# Signal_isolator.net
KiCad netlist of a schematic drawn in Altium Designer
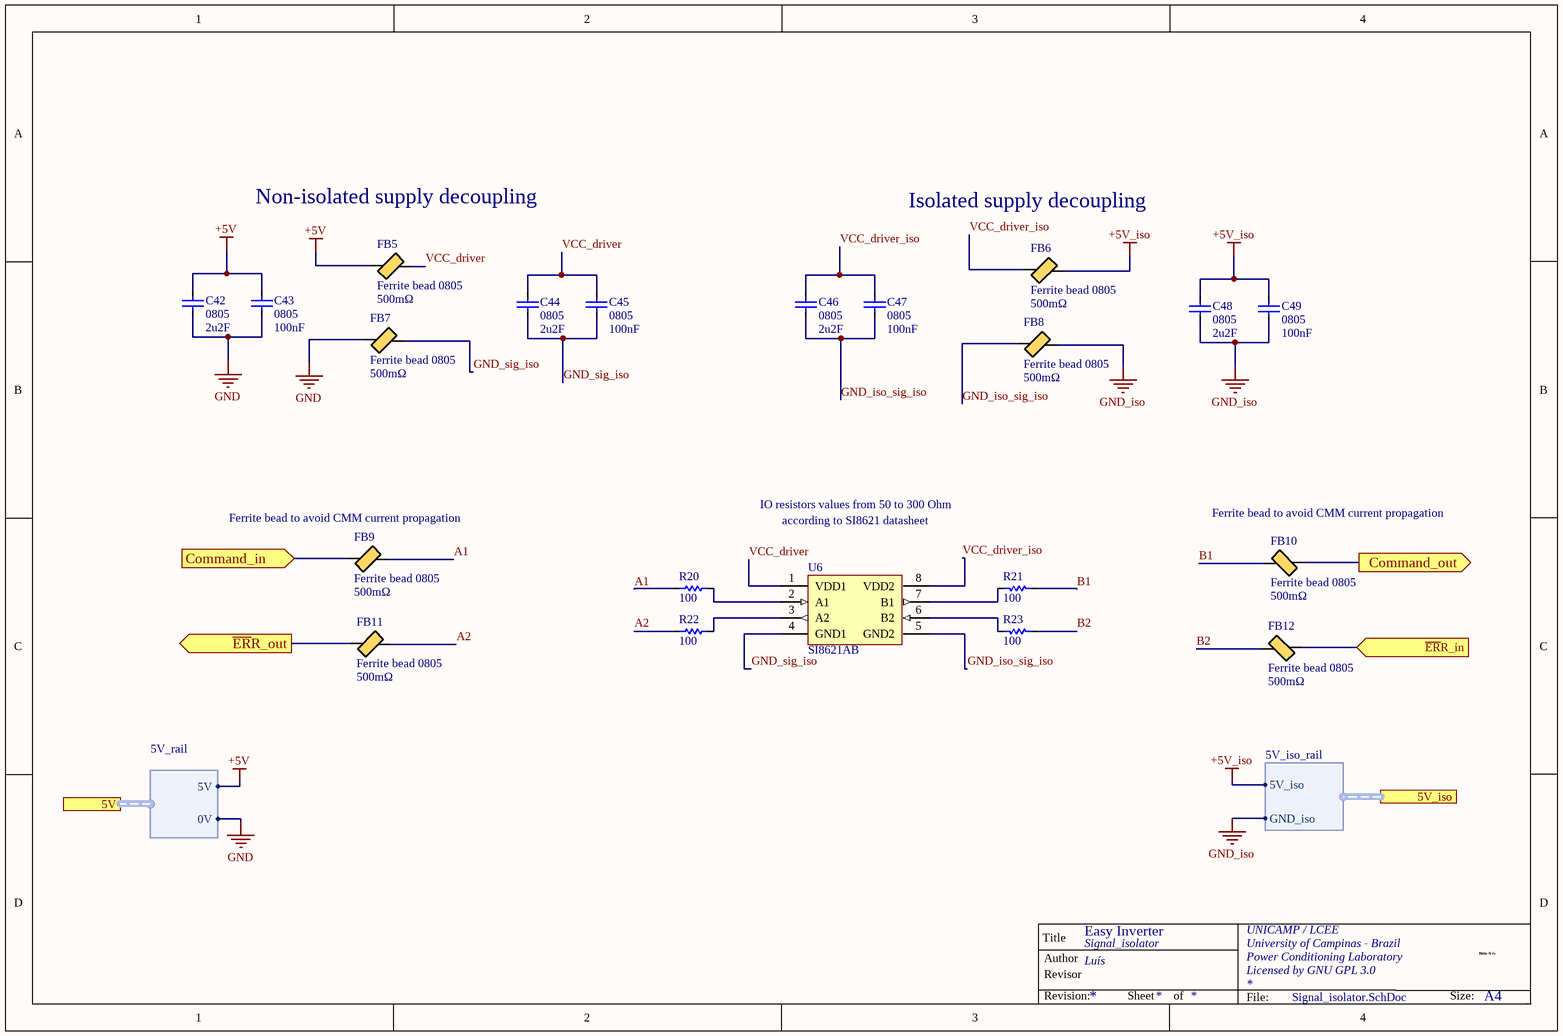
[diagram p0: Signal_isolator.SchDoc]

(export (version "E")
  (design (tool "Eeschema 10.0.6"))
  (components
    (comp (ref "C42")
      (value "0805")
      (footprint "Capacitor 0805")
      (description "SMD ceramic capacitor 0805")
      (fields (field (name "ALTIUM_VALUE") "2u2F"))
      (libsource (lib "EdgeInverter_library") (part "Capacitor 0805"))
    )
    (comp (ref "C43")
      (value "0805")
      (footprint "Capacitor 0805")
      (description "SMD ceramic capacitor 0805")
      (fields (field (name "ALTIUM_VALUE") "100nF"))
      (libsource (lib "EdgeInverter_library") (part "Capacitor 0805"))
    )
    (comp (ref "C44")
      (value "0805")
      (footprint "Capacitor 0805")
      (description "SMD ceramic capacitor 0805")
      (fields (field (name "ALTIUM_VALUE") "2u2F"))
      (libsource (lib "EdgeInverter_library") (part "Capacitor 0805"))
    )
    (comp (ref "C45")
      (value "0805")
      (footprint "Capacitor 0805")
      (description "SMD ceramic capacitor 0805")
      (fields (field (name "ALTIUM_VALUE") "100nF"))
      (libsource (lib "EdgeInverter_library") (part "Capacitor 0805"))
    )
    (comp (ref "C46")
      (value "0805")
      (footprint "Capacitor 0805")
      (description "SMD ceramic capacitor 0805")
      (fields (field (name "ALTIUM_VALUE") "2u2F"))
      (libsource (lib "EdgeInverter_library") (part "Capacitor 0805"))
    )
    (comp (ref "C47")
      (value "0805")
      (footprint "Capacitor 0805")
      (description "SMD ceramic capacitor 0805")
      (fields (field (name "ALTIUM_VALUE") "100nF"))
      (libsource (lib "EdgeInverter_library") (part "Capacitor 0805"))
    )
    (comp (ref "C48")
      (value "0805")
      (footprint "Capacitor 0805")
      (description "SMD ceramic capacitor 0805")
      (fields (field (name "ALTIUM_VALUE") "2u2F"))
      (libsource (lib "EdgeInverter_library") (part "Capacitor 0805"))
    )
    (comp (ref "C49")
      (value "0805")
      (footprint "Capacitor 0805")
      (description "SMD ceramic capacitor 0805")
      (fields (field (name "ALTIUM_VALUE") "100nF"))
      (libsource (lib "EdgeInverter_library") (part "Capacitor 0805"))
    )
    (comp (ref "FB5")
      (value "Ferrite bead 0805")
      (footprint "Bead 0805")
      (description "Ferrite bead chip 0805")
      (fields (field (name "DC RESISTANCE") "500mΩ"))
      (libsource (lib "EdgeInverter_library") (part "Ferrite_bead"))
    )
    (comp (ref "FB6")
      (value "Ferrite bead 0805")
      (footprint "Bead 0805")
      (description "Ferrite bead chip 0805")
      (fields (field (name "DC RESISTANCE") "500mΩ"))
      (libsource (lib "EdgeInverter_library") (part "Ferrite_bead"))
    )
    (comp (ref "FB7")
      (value "Ferrite bead 0805")
      (footprint "Bead 0805")
      (description "Ferrite bead chip 0805")
      (fields (field (name "DC RESISTANCE") "500mΩ"))
      (libsource (lib "EdgeInverter_library") (part "Ferrite_bead"))
    )
    (comp (ref "FB8")
      (value "Ferrite bead 0805")
      (footprint "Bead 0805")
      (description "Ferrite bead chip 0805")
      (fields (field (name "DC RESISTANCE") "500mΩ"))
      (libsource (lib "EdgeInverter_library") (part "Ferrite_bead"))
    )
    (comp (ref "FB9")
      (value "Ferrite bead 0805")
      (footprint "Bead 0805")
      (description "Ferrite bead chip 0805")
      (fields (field (name "DC RESISTANCE") "500mΩ"))
      (libsource (lib "EdgeInverter_library") (part "Ferrite_bead"))
    )
    (comp (ref "FB10")
      (value "Ferrite bead 0805")
      (footprint "Bead 0805")
      (description "Ferrite bead chip 0805")
      (fields (field (name "DC RESISTANCE") "500mΩ"))
      (libsource (lib "EdgeInverter_library") (part "Ferrite_bead"))
    )
    (comp (ref "FB11")
      (value "Ferrite bead 0805")
      (footprint "Bead 0805")
      (description "Ferrite bead chip 0805")
      (fields (field (name "DC RESISTANCE") "500mΩ"))
      (libsource (lib "EdgeInverter_library") (part "Ferrite_bead"))
    )
    (comp (ref "FB12")
      (value "Ferrite bead 0805")
      (footprint "Bead 0805")
      (description "Ferrite bead chip 0805")
      (fields (field (name "DC RESISTANCE") "500mΩ"))
      (libsource (lib "EdgeInverter_library") (part "Ferrite_bead"))
    )
    (comp (ref "R20")
      (value "100")
      (footprint "Resistor 0805")
      (description "SMD resistor 0805")
      (fields (field (name "Comment") "Resistor 0805"))
      (libsource (lib "EdgeInverter_library") (part "Resistor 0805"))
    )
    (comp (ref "R21")
      (value "100")
      (footprint "Resistor 0805")
      (description "SMD resistor 0805")
      (fields (field (name "Comment") "Resistor 0805"))
      (libsource (lib "EdgeInverter_library") (part "Resistor 0805"))
    )
    (comp (ref "R22")
      (value "100")
      (footprint "Resistor 0805")
      (description "SMD resistor 0805")
      (fields (field (name "Comment") "Resistor 0805"))
      (libsource (lib "EdgeInverter_library") (part "Resistor 0805"))
    )
    (comp (ref "R23")
      (value "100")
      (footprint "Resistor 0805")
      (description "SMD resistor 0805")
      (fields (field (name "Comment") "Resistor 0805"))
      (libsource (lib "EdgeInverter_library") (part "Resistor 0805"))
    )
    (comp (ref "U6")
      (value "SI8621AB")
      (footprint "SOIC 8")
      (description "Digital Isolator 2.5KV, general purpose 8SOIC")
      (libsource (lib "EdgeInverter_library") (part "SI8621AB"))
    )
  )
  (nets
    (net (code "3") (name "+5V") (class "Default")
      (node (ref "C42") (pin "1") (pinfunction "1_1") (pintype "passive"))
      (node (ref "C43") (pin "1") (pinfunction "1_1") (pintype "passive"))
      (node (ref "FB5") (pin "1") (pinfunction "1_1") (pintype "passive"))
    )
    (net (code "4") (name "+5V_iso") (class "Default")
      (node (ref "C48") (pin "1") (pinfunction "1_1") (pintype "passive"))
      (node (ref "C49") (pin "1") (pinfunction "1_1") (pintype "passive"))
      (node (ref "FB6") (pin "2") (pinfunction "2_2") (pintype "passive"))
    )
    (net (code "5") (name "/A1") (class "Default")
      (node (ref "FB9") (pin "2") (pinfunction "2_2") (pintype "passive"))
      (node (ref "R20") (pin "1") (pinfunction "1_1") (pintype "passive"))
    )
    (net (code "6") (name "/A2") (class "Default")
      (node (ref "FB11") (pin "2") (pinfunction "2_2") (pintype "passive"))
      (node (ref "R22") (pin "1") (pinfunction "1_1") (pintype "passive"))
    )
    (net (code "7") (name "/B1") (class "Default")
      (node (ref "FB10") (pin "2") (pinfunction "2_2") (pintype "passive"))
      (node (ref "R21") (pin "1") (pinfunction "1_1") (pintype "passive"))
    )
    (net (code "8") (name "/B2") (class "Default")
      (node (ref "FB12") (pin "2") (pinfunction "2_2") (pintype "passive"))
      (node (ref "R23") (pin "1") (pinfunction "1_1") (pintype "passive"))
    )
    (net (code "9") (name "/Command_in") (class "Default")
      (node (ref "FB9") (pin "1") (pinfunction "1_1") (pintype "passive"))
    )
    (net (code "10") (name "/Command_out") (class "Default")
      (node (ref "FB10") (pin "1") (pinfunction "1_1") (pintype "passive"))
    )
    (net (code "11") (name "/GND_iso_sig_iso") (class "Default")
      (node (ref "C46") (pin "2") (pinfunction "2_2") (pintype "passive"))
      (node (ref "C47") (pin "2") (pinfunction "2_2") (pintype "passive"))
      (node (ref "FB8") (pin "1") (pinfunction "1_1") (pintype "passive"))
      (node (ref "U6") (pin "5") (pinfunction "GND2_5") (pintype "power_in"))
    )
    (net (code "12") (name "/GND_sig_iso") (class "Default")
      (node (ref "C44") (pin "2") (pinfunction "2_2") (pintype "passive"))
      (node (ref "C45") (pin "2") (pinfunction "2_2") (pintype "passive"))
      (node (ref "FB7") (pin "2") (pinfunction "2_2") (pintype "passive"))
      (node (ref "U6") (pin "4") (pinfunction "GND1_4") (pintype "power_in"))
    )
    (net (code "13") (name "/VCC_driver") (class "Default")
      (node (ref "C44") (pin "1") (pinfunction "1_1") (pintype "passive"))
      (node (ref "C45") (pin "1") (pinfunction "1_1") (pintype "passive"))
      (node (ref "FB5") (pin "2") (pinfunction "2_2") (pintype "passive"))
      (node (ref "U6") (pin "1") (pinfunction "VDD1_1") (pintype "power_in"))
    )
    (net (code "14") (name "/VCC_driver_iso") (class "Default")
      (node (ref "C46") (pin "1") (pinfunction "1_1") (pintype "passive"))
      (node (ref "C47") (pin "1") (pinfunction "1_1") (pintype "passive"))
      (node (ref "FB6") (pin "1") (pinfunction "1_1") (pintype "passive"))
      (node (ref "U6") (pin "8") (pinfunction "VDD2_8") (pintype "power_in"))
    )
    (net (code "17") (name "/~{ER}R_in") (class "Default")
      (node (ref "FB12") (pin "1") (pinfunction "1_1") (pintype "passive"))
    )
    (net (code "18") (name "/~{ER}R_out") (class "Default")
      (node (ref "FB11") (pin "1") (pinfunction "1_1") (pintype "passive"))
    )
    (net (code "19") (name "GND") (class "Default")
      (node (ref "C42") (pin "2") (pinfunction "2_2") (pintype "passive"))
      (node (ref "C43") (pin "2") (pinfunction "2_2") (pintype "passive"))
      (node (ref "FB7") (pin "1") (pinfunction "1_1") (pintype "passive"))
    )
    (net (code "20") (name "GND_iso") (class "Default")
      (node (ref "C48") (pin "2") (pinfunction "2_2") (pintype "passive"))
      (node (ref "C49") (pin "2") (pinfunction "2_2") (pintype "passive"))
      (node (ref "FB8") (pin "2") (pinfunction "2_2") (pintype "passive"))
    )
    (net (code "21") (name "Net-(U6-A1)") (class "Default")
      (node (ref "R20") (pin "2") (pinfunction "2_2") (pintype "passive"))
      (node (ref "U6") (pin "2") (pinfunction "A1_2") (pintype "input"))
    )
    (net (code "22") (name "Net-(U6-A2)") (class "Default")
      (node (ref "R22") (pin "2") (pinfunction "2_2") (pintype "passive"))
      (node (ref "U6") (pin "3") (pinfunction "A2_3") (pintype "output"))
    )
    (net (code "23") (name "Net-(U6-B1)") (class "Default")
      (node (ref "R21") (pin "2") (pinfunction "2_2") (pintype "passive"))
      (node (ref "U6") (pin "7") (pinfunction "B1_7") (pintype "output"))
    )
    (net (code "24") (name "Net-(U6-B2)") (class "Default")
      (node (ref "R23") (pin "2") (pinfunction "2_2") (pintype "passive"))
      (node (ref "U6") (pin "6") (pinfunction "B2_6") (pintype "input"))
    )
  )
)
